# PowerScr.net
KiCad netlist of a schematic drawn in Altium Designer
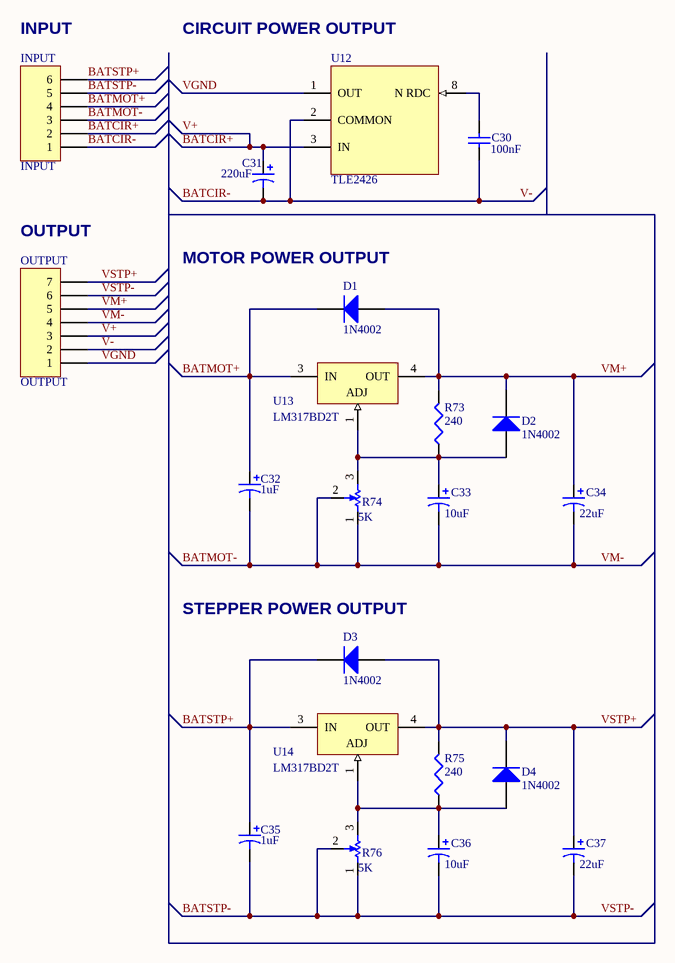
[diagram p0: PowerScr.SchDoc]

(export (version "E")
  (design (tool "Eeschema 10.0.6"))
  (components
    (comp (ref "C30")
      (value "100nF")
      (footprint "RAD-0.2")
      (description "Capacitor")
      (fields (field (name "Comment") "Cap") (field (name "PUBLISHER") "Altium Limited"))
      (libsource (lib "Miscellaneous Devices") (part "Cap"))
    )
    (comp (ref "C31")
      (value "220uF")
      (footprint "C100UFB")
      (description "Polarized Capacitor (Radial)")
      (fields (field (name "Comment") "Cap Pol1") (field (name "PUBLISHER") "Altium Limited"))
      (libsource (lib "Miscellaneous Devices") (part "Cap Pol1"))
    )
    (comp (ref "C32")
      (value "1uF")
      (footprint "3528")
      (fields (field (name "Comment") "593D105X0020B2") (field (name "PUBLISHER") "Altium Limited"))
      (libsource (lib "Vishay Sprague Tantalum Chip Capacitor") (part "593D106X0020B2"))
    )
    (comp (ref "C33")
      (value "10uF")
      (footprint "7343")
      (fields (field (name "Comment") "593D226X0020D2") (field (name "PUBLISHER") "Altium Limited"))
      (libsource (lib "Vishay Sprague Tantalum Chip Capacitor") (part "593D226X0020D2"))
    )
    (comp (ref "C34")
      (value "22uF")
      (footprint "7343")
      (fields (field (name "Comment") "593D226X0020D2") (field (name "PUBLISHER") "Altium Limited"))
      (libsource (lib "Vishay Sprague Tantalum Chip Capacitor") (part "593D226X0020D2"))
    )
    (comp (ref "C35")
      (value "1uF")
      (footprint "3528")
      (fields (field (name "Comment") "593D105X0020B2") (field (name "PUBLISHER") "Altium Limited"))
      (libsource (lib "Vishay Sprague Tantalum Chip Capacitor") (part "593D106X0020B2"))
    )
    (comp (ref "C36")
      (value "10uF")
      (footprint "7343")
      (fields (field (name "Comment") "593D226X0020D2") (field (name "PUBLISHER") "Altium Limited"))
      (libsource (lib "Vishay Sprague Tantalum Chip Capacitor") (part "593D226X0020D2"))
    )
    (comp (ref "C37")
      (value "22uF")
      (footprint "7343")
      (fields (field (name "Comment") "593D226X0020D2") (field (name "PUBLISHER") "Altium Limited"))
      (libsource (lib "Vishay Sprague Tantalum Chip Capacitor") (part "593D226X0020D2"))
    )
    (comp (ref "D1")
      (value "1N4002")
      (footprint "DO-41")
      (description "1 Amp General Purpose Rectifier")
      (fields (field (name "PUBLISHER") "Altium Limited"))
      (libsource (lib "Miscellaneous Devices") (part "Diode 1N4002"))
    )
    (comp (ref "D2")
      (value "1N4002")
      (footprint "DO-41")
      (description "1 Amp General Purpose Rectifier")
      (fields (field (name "PUBLISHER") "Altium Limited"))
      (libsource (lib "Miscellaneous Devices") (part "Diode 1N4002"))
    )
    (comp (ref "D3")
      (value "1N4002")
      (footprint "DO-41")
      (description "1 Amp General Purpose Rectifier")
      (fields (field (name "PUBLISHER") "Altium Limited"))
      (libsource (lib "Miscellaneous Devices") (part "Diode 1N4002"))
    )
    (comp (ref "D4")
      (value "1N4002")
      (footprint "DO-41")
      (description "1 Amp General Purpose Rectifier")
      (fields (field (name "PUBLISHER") "Altium Limited"))
      (libsource (lib "Miscellaneous Devices") (part "Diode 1N4002"))
    )
    (comp (ref "INPUT")
      (value "INPUT")
      (footprint "AZUL5-6")
      (description "Header, 6-Pin")
      (fields (field (name "PUBLISHER") "Altium Limited"))
      (libsource (lib "Miscellaneous Connectors") (part "Header 6"))
    )
    (comp (ref "OUTPUT")
      (value "OUTPUT")
      (footprint "AZUL5-7")
      (description "Header, 7-Pin")
      (fields (field (name "PUBLISHER") "Altium Limited"))
      (libsource (lib "Miscellaneous Connectors") (part "Header 7"))
    )
    (comp (ref "R73")
      (value "240")
      (footprint "RESC6332M")
      (description "Resistor")
      (fields (field (name "Comment") "Res3") (field (name "PUBLISHER") "Altium Limited"))
      (libsource (lib "Miscellaneous Devices") (part "Res3"))
    )
    (comp (ref "R74")
      (value "5K")
      (footprint "3361P")
      (fields (field (name "Comment") "POT3361"))
      (libsource (lib "LitoLibrary") (part "POT3361"))
    )
    (comp (ref "R75")
      (value "240")
      (footprint "RESC6332M")
      (description "Resistor")
      (fields (field (name "Comment") "Res3") (field (name "PUBLISHER") "Altium Limited"))
      (libsource (lib "Miscellaneous Devices") (part "Res3"))
    )
    (comp (ref "R76")
      (value "5K")
      (footprint "3361P")
      (fields (field (name "Comment") "POT3361"))
      (libsource (lib "LitoLibrary") (part "POT3361"))
    )
    (comp (ref "U12")
      (value "TLE2426")
      (footprint "SOP8 - duplicate")
      (description "Precision Virtual Ground")
      (libsource (lib "LitoLibrary") (part "TLE2426"))
    )
    (comp (ref "U13")
      (value "LM317BD2T")
      (footprint "936-03")
      (description "Three-Terminal Adjustable Output Positive Voltage Regulator")
      (fields (field (name "PUBLISHER") "Altium Limited"))
      (libsource (lib "ON Semi Power Mgt Voltage Regulator") (part "LM317BD2T"))
    )
    (comp (ref "U14")
      (value "LM317BD2T")
      (footprint "936-03")
      (description "Three-Terminal Adjustable Output Positive Voltage Regulator")
      (fields (field (name "PUBLISHER") "Altium Limited"))
      (libsource (lib "ON Semi Power Mgt Voltage Regulator") (part "LM317BD2T"))
    )
  )
  (nets
    (net (code "1") (name "/BATCIR+") (class "Default")
      (node (ref "C31") (pin "1") (pinfunction "1_1") (pintype "passive"))
      (node (ref "INPUT") (pin "2") (pinfunction "2_2") (pintype "passive"))
      (node (ref "OUTPUT") (pin "3") (pinfunction "3_3") (pintype "passive"))
      (node (ref "U12") (pin "3") (pinfunction "IN_3") (pintype "passive"))
    )
    (net (code "2") (name "/BATCIR-") (class "Default")
      (node (ref "C30") (pin "1") (pinfunction "1_1") (pintype "passive"))
      (node (ref "C31") (pin "2") (pinfunction "2_2") (pintype "passive"))
      (node (ref "INPUT") (pin "1") (pinfunction "1_1") (pintype "passive"))
      (node (ref "OUTPUT") (pin "2") (pinfunction "2_2") (pintype "passive"))
      (node (ref "U12") (pin "2") (pinfunction "COMMON_2") (pintype "passive"))
    )
    (net (code "3") (name "/BATMOT+") (class "Default")
      (node (ref "C32") (pin "1") (pinfunction "1_1") (pintype "passive"))
      (node (ref "D1") (pin "2") (pinfunction "K_2") (pintype "passive"))
      (node (ref "INPUT") (pin "4") (pinfunction "4_4") (pintype "passive"))
      (node (ref "U13") (pin "3") (pinfunction "IN_3") (pintype "power_in"))
    )
    (net (code "4") (name "/BATMOT-") (class "Default")
      (node (ref "C32") (pin "2") (pinfunction "2_2") (pintype "passive"))
      (node (ref "C33") (pin "2") (pinfunction "2_2") (pintype "passive"))
      (node (ref "C34") (pin "2") (pinfunction "2_2") (pintype "passive"))
      (node (ref "INPUT") (pin "3") (pinfunction "3_3") (pintype "passive"))
      (node (ref "OUTPUT") (pin "4") (pinfunction "4_4") (pintype "passive"))
      (node (ref "R74") (pin "1") (pinfunction "1_1") (pintype "passive"))
      (node (ref "R74") (pin "2") (pinfunction "2_2") (pintype "passive"))
    )
    (net (code "5") (name "/BATSTP+") (class "Default")
      (node (ref "C35") (pin "1") (pinfunction "1_1") (pintype "passive"))
      (node (ref "D3") (pin "2") (pinfunction "K_2") (pintype "passive"))
      (node (ref "INPUT") (pin "6") (pinfunction "6_6") (pintype "passive"))
      (node (ref "U14") (pin "3") (pinfunction "IN_3") (pintype "power_in"))
    )
    (net (code "6") (name "/BATSTP-") (class "Default")
      (node (ref "C35") (pin "2") (pinfunction "2_2") (pintype "passive"))
      (node (ref "C36") (pin "2") (pinfunction "2_2") (pintype "passive"))
      (node (ref "C37") (pin "2") (pinfunction "2_2") (pintype "passive"))
      (node (ref "INPUT") (pin "5") (pinfunction "5_5") (pintype "passive"))
      (node (ref "OUTPUT") (pin "6") (pinfunction "6_6") (pintype "passive"))
      (node (ref "R76") (pin "1") (pinfunction "1_1") (pintype "passive"))
      (node (ref "R76") (pin "2") (pinfunction "2_2") (pintype "passive"))
    )
    (net (code "7") (name "/VGND") (class "Default")
      (node (ref "OUTPUT") (pin "1") (pinfunction "1_1") (pintype "passive"))
      (node (ref "U12") (pin "1") (pinfunction "OUT_1") (pintype "passive"))
    )
    (net (code "8") (name "/VM+") (class "Default")
      (node (ref "C34") (pin "1") (pinfunction "1_1") (pintype "passive"))
      (node (ref "D1") (pin "1") (pinfunction "A_1") (pintype "passive"))
      (node (ref "D2") (pin "2") (pinfunction "K_2") (pintype "passive"))
      (node (ref "OUTPUT") (pin "5") (pinfunction "5_5") (pintype "passive"))
      (node (ref "R73") (pin "2") (pinfunction "2_2") (pintype "passive"))
      (node (ref "U13") (pin "4") (pinfunction "OUT_4") (pintype "power_in"))
    )
    (net (code "9") (name "/VSTP+") (class "Default")
      (node (ref "C37") (pin "1") (pinfunction "1_1") (pintype "passive"))
      (node (ref "D3") (pin "1") (pinfunction "A_1") (pintype "passive"))
      (node (ref "D4") (pin "2") (pinfunction "K_2") (pintype "passive"))
      (node (ref "OUTPUT") (pin "7") (pinfunction "7_7") (pintype "passive"))
      (node (ref "R75") (pin "2") (pinfunction "2_2") (pintype "passive"))
      (node (ref "U14") (pin "4") (pinfunction "OUT_4") (pintype "power_in"))
    )
    (net (code "10") (name "Net-(D2-A)") (class "Default")
      (node (ref "C33") (pin "1") (pinfunction "1_1") (pintype "passive"))
      (node (ref "D2") (pin "1") (pinfunction "A_1") (pintype "passive"))
      (node (ref "R73") (pin "1") (pinfunction "1_1") (pintype "passive"))
      (node (ref "R74") (pin "3") (pinfunction "3_3") (pintype "passive"))
      (node (ref "U13") (pin "1") (pinfunction "ADJ_1") (pintype "input"))
    )
    (net (code "11") (name "Net-(D4-A)") (class "Default")
      (node (ref "C36") (pin "1") (pinfunction "1_1") (pintype "passive"))
      (node (ref "D4") (pin "1") (pinfunction "A_1") (pintype "passive"))
      (node (ref "R75") (pin "1") (pinfunction "1_1") (pintype "passive"))
      (node (ref "R76") (pin "3") (pinfunction "3_3") (pintype "passive"))
      (node (ref "U14") (pin "1") (pinfunction "ADJ_1") (pintype "input"))
    )
    (net (code "12") (name "Net-(U12-N_RDC)") (class "Default")
      (node (ref "C30") (pin "2") (pinfunction "2_2") (pintype "passive"))
      (node (ref "U12") (pin "8") (pinfunction "N_RDC_8") (pintype "input"))
    )
    (net (code "13") (name "unconnected-(U12-NC-Pad4)") (class "Default")
      (node (ref "U12") (pin "4") (pinfunction "NC_4") (pintype "passive"))
    )
    (net (code "14") (name "unconnected-(U12-NC-Pad5)") (class "Default")
      (node (ref "U12") (pin "5") (pinfunction "NC_5") (pintype "passive"))
    )
    (net (code "15") (name "unconnected-(U12-NC-Pad6)") (class "Default")
      (node (ref "U12") (pin "6") (pinfunction "NC_6") (pintype "passive"))
    )
    (net (code "16") (name "unconnected-(U12-NC-Pad7)") (class "Default")
      (node (ref "U12") (pin "7") (pinfunction "NC_7") (pintype "passive"))
    )
  )
)
